# can-weichendecoder-magnet.net
KiCad netlist of a schematic drawn in EAGLE
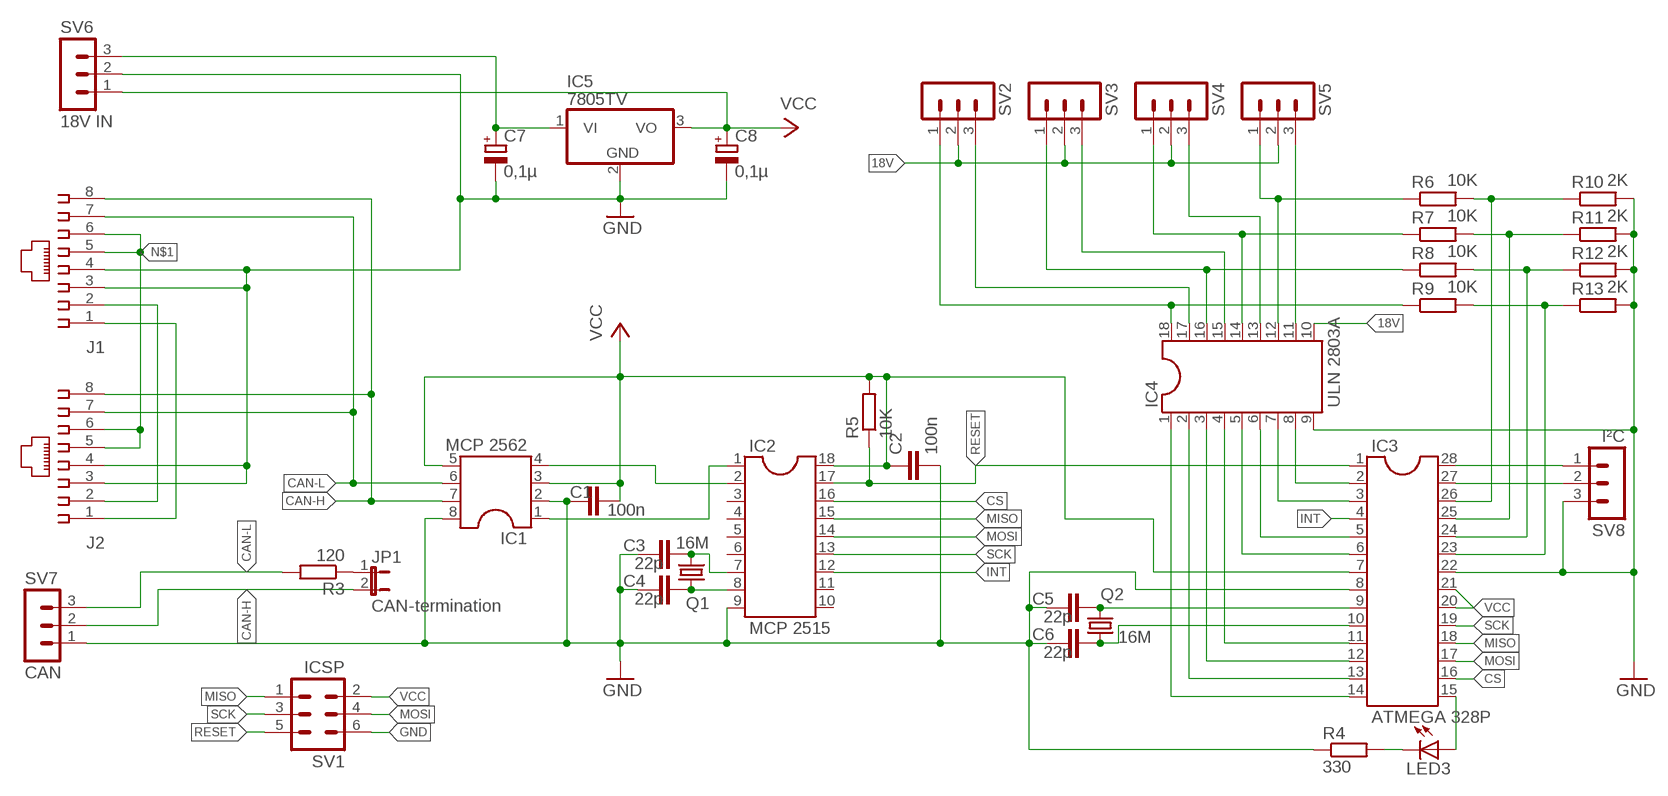
[diagram p0: schematic, sheet 1]

(export (version "E")
  (design (tool "Eeschema 10.0.6"))
  (components
    (comp (ref "C1")
      (value "100n")
      (footprint "eagle-import:C2.5-2")
      (libsource (lib "eagle-import") (part "C2.5/2"))
    )
    (comp (ref "C2")
      (value "100n")
      (footprint "eagle-import:C2.5-2")
      (libsource (lib "eagle-import") (part "C2.5/2"))
    )
    (comp (ref "C3")
      (value "22p")
      (footprint "eagle-import:C2.5-2")
      (libsource (lib "eagle-import") (part "C2.5/2"))
    )
    (comp (ref "C4")
      (value "22p")
      (footprint "eagle-import:C2.5-2")
      (libsource (lib "eagle-import") (part "C2.5/2"))
    )
    (comp (ref "C5")
      (value "22p")
      (footprint "eagle-import:C2.5-2")
      (libsource (lib "eagle-import") (part "C2.5/2"))
    )
    (comp (ref "C6")
      (value "22p")
      (footprint "eagle-import:C2.5-2")
      (libsource (lib "eagle-import") (part "C2.5/2"))
    )
    (comp (ref "C7")
      (value "0,1µ")
      (footprint "eagle-import:E2,5-6")
      (libsource (lib "eagle-import") (part "CPOL-EUE2.5-6"))
    )
    (comp (ref "C8")
      (value "0,1µ")
      (footprint "eagle-import:E2,5-6")
      (libsource (lib "eagle-import") (part "CPOL-EUE2.5-6"))
    )
    (comp (ref "IC1")
      (value "MCP 2562")
      (footprint "eagle-import:SOCKET-08")
      (libsource (lib "eagle-import") (part "DIL8S"))
    )
    (comp (ref "IC2")
      (value "MCP 2515")
      (footprint "eagle-import:SOCKET-18")
      (libsource (lib "eagle-import") (part "DIL18S"))
    )
    (comp (ref "IC3")
      (value "ATMEGA 328P")
      (footprint "eagle-import:DIL28-3")
      (libsource (lib "eagle-import") (part "DIL28-3"))
    )
    (comp (ref "IC4")
      (value "ULN 2803A")
      (footprint "eagle-import:SOCKET-18")
      (libsource (lib "eagle-import") (part "DIL18S"))
    )
    (comp (ref "IC5")
      (value "7805TV")
      (footprint "eagle-import:TO220V")
      (libsource (lib "eagle-import") (part "78TV05"))
    )
    (comp (ref "J1")
      (value "215877-7")
      (footprint "eagle-import:215877-7")
      (libsource (lib "eagle-import") (part "215877-7"))
    )
    (comp (ref "J2")
      (value "215877-7")
      (footprint "eagle-import:215877-7")
      (libsource (lib "eagle-import") (part "215877-7"))
    )
    (comp (ref "JP1")
      (value "CAN-termination")
      (footprint "eagle-import:JP1")
      (libsource (lib "eagle-import") (part "JP1E"))
    )
    (comp (ref "LED3")
      (value "LED5MM")
      (footprint "eagle-import:LED5MM")
      (libsource (lib "eagle-import") (part "LED5MM"))
    )
    (comp (ref "Q1")
      (value "16M")
      (footprint "eagle-import:HC49_S")
      (libsource (lib "eagle-import") (part "CRYSTALHC49S"))
    )
    (comp (ref "Q2")
      (value "16M")
      (footprint "eagle-import:HC49_S")
      (libsource (lib "eagle-import") (part "CRYSTALHC49S"))
    )
    (comp (ref "R3")
      (value "120")
      (footprint "eagle-import:0207_10")
      (libsource (lib "eagle-import") (part "R-EU_0207/10"))
    )
    (comp (ref "R4")
      (value "330")
      (footprint "eagle-import:0207_10")
      (libsource (lib "eagle-import") (part "R-EU_0207/10"))
    )
    (comp (ref "R5")
      (value "10K")
      (footprint "eagle-import:0207_10")
      (libsource (lib "eagle-import") (part "R-EU_0207/10"))
    )
    (comp (ref "R6")
      (value "10K")
      (footprint "eagle-import:0207_10")
      (libsource (lib "eagle-import") (part "R-EU_0207/10"))
    )
    (comp (ref "R7")
      (value "10K")
      (footprint "eagle-import:0207_10")
      (libsource (lib "eagle-import") (part "R-EU_0207/10"))
    )
    (comp (ref "R8")
      (value "10K")
      (footprint "eagle-import:0207_10")
      (libsource (lib "eagle-import") (part "R-EU_0207/10"))
    )
    (comp (ref "R9")
      (value "10K")
      (footprint "eagle-import:0207_10")
      (libsource (lib "eagle-import") (part "R-EU_0207/10"))
    )
    (comp (ref "R10")
      (value "2K")
      (footprint "eagle-import:0207_10")
      (libsource (lib "eagle-import") (part "R-EU_0207/10"))
    )
    (comp (ref "R11")
      (value "2K")
      (footprint "eagle-import:0207_10")
      (libsource (lib "eagle-import") (part "R-EU_0207/10"))
    )
    (comp (ref "R12")
      (value "2K")
      (footprint "eagle-import:0207_10")
      (libsource (lib "eagle-import") (part "R-EU_0207/10"))
    )
    (comp (ref "R13")
      (value "2K")
      (footprint "eagle-import:0207_10")
      (libsource (lib "eagle-import") (part "R-EU_0207/10"))
    )
    (comp (ref "SV1")
      (value "ICSP")
      (footprint "eagle-import:MA03-2")
      (libsource (lib "eagle-import") (part "MA03-2"))
    )
    (comp (ref "SV2")
      (value "MA03-1")
      (footprint "eagle-import:MA03-1")
      (libsource (lib "eagle-import") (part "MA03-1"))
    )
    (comp (ref "SV3")
      (value "MA03-1")
      (footprint "eagle-import:MA03-1")
      (libsource (lib "eagle-import") (part "MA03-1"))
    )
    (comp (ref "SV4")
      (value "MA03-1")
      (footprint "eagle-import:MA03-1")
      (libsource (lib "eagle-import") (part "MA03-1"))
    )
    (comp (ref "SV5")
      (value "MA03-1")
      (footprint "eagle-import:MA03-1")
      (libsource (lib "eagle-import") (part "MA03-1"))
    )
    (comp (ref "SV6")
      (value "18V IN")
      (footprint "eagle-import:MA03-1")
      (libsource (lib "eagle-import") (part "MA03-1"))
    )
    (comp (ref "SV7")
      (value "CAN")
      (footprint "eagle-import:MA03-1")
      (libsource (lib "eagle-import") (part "MA03-1"))
    )
    (comp (ref "SV8")
      (value "I²C")
      (footprint "eagle-import:MA03-1")
      (libsource (lib "eagle-import") (part "MA03-1"))
    )
  )
  (nets
    (net (code "1") (name "18V") (class "Default")
      (node (ref "C7") (pin "+") (pinfunction "+_+") (pintype "passive"))
      (node (ref "IC4") (pin "10") (pinfunction "10_10") (pintype "passive"))
      (node (ref "IC5") (pin "1") (pinfunction "VI_1") (pintype "input"))
      (node (ref "SV2") (pin "2") (pinfunction "2_2") (pintype "passive"))
      (node (ref "SV3") (pin "2") (pinfunction "2_2") (pintype "passive"))
      (node (ref "SV4") (pin "2") (pinfunction "2_2") (pintype "passive"))
      (node (ref "SV5") (pin "2") (pinfunction "2_2") (pintype "passive"))
      (node (ref "SV6") (pin "3") (pinfunction "3_3") (pintype "passive"))
    )
    (net (code "2") (name "CAN-H") (class "Default")
      (node (ref "IC1") (pin "7") (pinfunction "7_7") (pintype "passive"))
      (node (ref "J1") (pin "8") (pinfunction "8_8") (pintype "passive"))
      (node (ref "J2") (pin "8") (pinfunction "8_8") (pintype "passive"))
      (node (ref "JP1") (pin "2") (pinfunction "2_2") (pintype "passive"))
      (node (ref "SV7") (pin "2") (pinfunction "2_2") (pintype "passive"))
    )
    (net (code "3") (name "CAN-L") (class "Default")
      (node (ref "IC1") (pin "6") (pinfunction "6_6") (pintype "passive"))
      (node (ref "J1") (pin "7") (pinfunction "7_7") (pintype "passive"))
      (node (ref "J2") (pin "7") (pinfunction "7_7") (pintype "passive"))
      (node (ref "R3") (pin "2") (pinfunction "2_2") (pintype "passive"))
      (node (ref "SV7") (pin "3") (pinfunction "3_3") (pintype "passive"))
    )
    (net (code "4") (name "CS") (class "Default")
      (node (ref "IC2") (pin "16") (pinfunction "16_16") (pintype "passive"))
      (node (ref "IC3") (pin "16") (pinfunction "16_16") (pintype "passive"))
    )
    (net (code "5") (name "GND") (class "Default")
      (node (ref "C1") (pin "1") (pinfunction "1_1") (pintype "passive"))
      (node (ref "C2") (pin "2") (pinfunction "2_2") (pintype "passive"))
      (node (ref "C3") (pin "1") (pinfunction "1_1") (pintype "passive"))
      (node (ref "C4") (pin "1") (pinfunction "1_1") (pintype "passive"))
      (node (ref "C5") (pin "1") (pinfunction "1_1") (pintype "passive"))
      (node (ref "C6") (pin "1") (pinfunction "1_1") (pintype "passive"))
      (node (ref "C7") (pin "-") (pinfunction "-_-") (pintype "passive"))
      (node (ref "C8") (pin "-") (pinfunction "-_-") (pintype "passive"))
      (node (ref "IC1") (pin "2") (pinfunction "2_2") (pintype "passive"))
      (node (ref "IC1") (pin "8") (pinfunction "8_8") (pintype "passive"))
      (node (ref "IC2") (pin "9") (pinfunction "9_9") (pintype "passive"))
      (node (ref "IC3") (pin "22") (pinfunction "22_22") (pintype "passive"))
      (node (ref "IC3") (pin "8") (pinfunction "8_8") (pintype "passive"))
      (node (ref "IC4") (pin "9") (pinfunction "9_9") (pintype "passive"))
      (node (ref "IC5") (pin "2") (pinfunction "GND_2") (pintype "passive"))
      (node (ref "J1") (pin "3") (pinfunction "3_3") (pintype "passive"))
      (node (ref "J1") (pin "4") (pinfunction "4_4") (pintype "passive"))
      (node (ref "J2") (pin "3") (pinfunction "3_3") (pintype "passive"))
      (node (ref "J2") (pin "4") (pinfunction "4_4") (pintype "passive"))
      (node (ref "R10") (pin "2") (pinfunction "2_2") (pintype "passive"))
      (node (ref "R11") (pin "2") (pinfunction "2_2") (pintype "passive"))
      (node (ref "R12") (pin "2") (pinfunction "2_2") (pintype "passive"))
      (node (ref "R13") (pin "2") (pinfunction "2_2") (pintype "passive"))
      (node (ref "R4") (pin "1") (pinfunction "1_1") (pintype "passive"))
      (node (ref "SV1") (pin "6") (pinfunction "6_6") (pintype "passive"))
      (node (ref "SV6") (pin "2") (pinfunction "2_2") (pintype "passive"))
      (node (ref "SV7") (pin "1") (pinfunction "1_1") (pintype "passive"))
      (node (ref "SV8") (pin "3") (pinfunction "3_3") (pintype "passive"))
    )
    (net (code "6") (name "INT") (class "Default")
      (node (ref "IC2") (pin "12") (pinfunction "12_12") (pintype "passive"))
      (node (ref "IC3") (pin "4") (pinfunction "4_4") (pintype "passive"))
    )
    (net (code "7") (name "MISO") (class "Default")
      (node (ref "IC2") (pin "15") (pinfunction "15_15") (pintype "passive"))
      (node (ref "IC3") (pin "18") (pinfunction "18_18") (pintype "passive"))
      (node (ref "SV1") (pin "1") (pinfunction "1_1") (pintype "passive"))
    )
    (net (code "8") (name "MOSI") (class "Default")
      (node (ref "IC2") (pin "14") (pinfunction "14_14") (pintype "passive"))
      (node (ref "IC3") (pin "17") (pinfunction "17_17") (pintype "passive"))
      (node (ref "SV1") (pin "4") (pinfunction "4_4") (pintype "passive"))
    )
    (net (code "9") (name "N$1") (class "Default")
      (node (ref "J1") (pin "5") (pinfunction "5_5") (pintype "passive"))
      (node (ref "J1") (pin "6") (pinfunction "6_6") (pintype "passive"))
      (node (ref "J2") (pin "5") (pinfunction "5_5") (pintype "passive"))
      (node (ref "J2") (pin "6") (pinfunction "6_6") (pintype "passive"))
    )
    (net (code "10") (name "Net-(C3-Pad2)") (class "Default")
      (node (ref "C3") (pin "2") (pinfunction "2_2") (pintype "passive"))
      (node (ref "IC2") (pin "7") (pinfunction "7_7") (pintype "passive"))
      (node (ref "Q1") (pin "2") (pinfunction "2_2") (pintype "passive"))
    )
    (net (code "11") (name "Net-(C4-Pad2)") (class "Default")
      (node (ref "C4") (pin "2") (pinfunction "2_2") (pintype "passive"))
      (node (ref "IC2") (pin "8") (pinfunction "8_8") (pintype "passive"))
      (node (ref "Q1") (pin "1") (pinfunction "1_1") (pintype "passive"))
    )
    (net (code "12") (name "Net-(C5-Pad2)") (class "Default")
      (node (ref "C5") (pin "2") (pinfunction "2_2") (pintype "passive"))
      (node (ref "IC3") (pin "9") (pinfunction "9_9") (pintype "passive"))
      (node (ref "Q2") (pin "2") (pinfunction "2_2") (pintype "passive"))
    )
    (net (code "13") (name "Net-(C6-Pad2)") (class "Default")
      (node (ref "C6") (pin "2") (pinfunction "2_2") (pintype "passive"))
      (node (ref "IC3") (pin "10") (pinfunction "10_10") (pintype "passive"))
      (node (ref "Q2") (pin "1") (pinfunction "1_1") (pintype "passive"))
    )
    (net (code "14") (name "Net-(IC1-Pad1)") (class "Default")
      (node (ref "IC1") (pin "1") (pinfunction "1_1") (pintype "passive"))
      (node (ref "IC2") (pin "1") (pinfunction "1_1") (pintype "passive"))
    )
    (net (code "15") (name "Net-(IC1-Pad4)") (class "Default")
      (node (ref "IC1") (pin "4") (pinfunction "4_4") (pintype "passive"))
      (node (ref "IC2") (pin "2") (pinfunction "2_2") (pintype "passive"))
    )
    (net (code "16") (name "Net-(IC3-Pad2)") (class "Default")
      (node (ref "IC3") (pin "2") (pinfunction "2_2") (pintype "passive"))
      (node (ref "IC4") (pin "8") (pinfunction "8_8") (pintype "passive"))
    )
    (net (code "17") (name "Net-(IC3-Pad3)") (class "Default")
      (node (ref "IC3") (pin "3") (pinfunction "3_3") (pintype "passive"))
      (node (ref "IC4") (pin "7") (pinfunction "7_7") (pintype "passive"))
    )
    (net (code "18") (name "Net-(IC3-Pad5)") (class "Default")
      (node (ref "IC3") (pin "5") (pinfunction "5_5") (pintype "passive"))
      (node (ref "IC4") (pin "6") (pinfunction "6_6") (pintype "passive"))
    )
    (net (code "19") (name "Net-(IC3-Pad6)") (class "Default")
      (node (ref "IC3") (pin "6") (pinfunction "6_6") (pintype "passive"))
      (node (ref "IC4") (pin "5") (pinfunction "5_5") (pintype "passive"))
    )
    (net (code "20") (name "Net-(IC3-Pad11)") (class "Default")
      (node (ref "IC3") (pin "11") (pinfunction "11_11") (pintype "passive"))
      (node (ref "IC4") (pin "4") (pinfunction "4_4") (pintype "passive"))
    )
    (net (code "21") (name "Net-(IC3-Pad12)") (class "Default")
      (node (ref "IC3") (pin "12") (pinfunction "12_12") (pintype "passive"))
      (node (ref "IC4") (pin "3") (pinfunction "3_3") (pintype "passive"))
    )
    (net (code "22") (name "Net-(IC3-Pad13)") (class "Default")
      (node (ref "IC3") (pin "13") (pinfunction "13_13") (pintype "passive"))
      (node (ref "IC4") (pin "2") (pinfunction "2_2") (pintype "passive"))
    )
    (net (code "23") (name "Net-(IC3-Pad14)") (class "Default")
      (node (ref "IC3") (pin "14") (pinfunction "14_14") (pintype "passive"))
      (node (ref "IC4") (pin "1") (pinfunction "1_1") (pintype "passive"))
    )
    (net (code "24") (name "Net-(IC3-Pad15)") (class "Default")
      (node (ref "IC3") (pin "15") (pinfunction "15_15") (pintype "passive"))
      (node (ref "LED3") (pin "A") (pinfunction "A_A") (pintype "passive"))
    )
    (net (code "25") (name "Net-(IC3-Pad23)") (class "Default")
      (node (ref "IC3") (pin "23") (pinfunction "23_23") (pintype "passive"))
      (node (ref "R13") (pin "1") (pinfunction "1_1") (pintype "passive"))
      (node (ref "R9") (pin "2") (pinfunction "2_2") (pintype "passive"))
    )
    (net (code "26") (name "Net-(IC3-Pad24)") (class "Default")
      (node (ref "IC3") (pin "24") (pinfunction "24_24") (pintype "passive"))
      (node (ref "R12") (pin "1") (pinfunction "1_1") (pintype "passive"))
      (node (ref "R8") (pin "2") (pinfunction "2_2") (pintype "passive"))
    )
    (net (code "27") (name "Net-(IC3-Pad25)") (class "Default")
      (node (ref "IC3") (pin "25") (pinfunction "25_25") (pintype "passive"))
      (node (ref "R11") (pin "1") (pinfunction "1_1") (pintype "passive"))
      (node (ref "R7") (pin "2") (pinfunction "2_2") (pintype "passive"))
    )
    (net (code "28") (name "Net-(IC3-Pad26)") (class "Default")
      (node (ref "IC3") (pin "26") (pinfunction "26_26") (pintype "passive"))
      (node (ref "R10") (pin "1") (pinfunction "1_1") (pintype "passive"))
      (node (ref "R6") (pin "2") (pinfunction "2_2") (pintype "passive"))
    )
    (net (code "29") (name "Net-(IC3-Pad27)") (class "Default")
      (node (ref "IC3") (pin "27") (pinfunction "27_27") (pintype "passive"))
      (node (ref "SV8") (pin "2") (pinfunction "2_2") (pintype "passive"))
    )
    (net (code "30") (name "Net-(IC3-Pad28)") (class "Default")
      (node (ref "IC3") (pin "28") (pinfunction "28_28") (pintype "passive"))
      (node (ref "SV8") (pin "1") (pinfunction "1_1") (pintype "passive"))
    )
    (net (code "31") (name "Net-(IC4-Pad11)") (class "Default")
      (node (ref "IC4") (pin "11") (pinfunction "11_11") (pintype "passive"))
      (node (ref "SV5") (pin "3") (pinfunction "3_3") (pintype "passive"))
    )
    (net (code "32") (name "Net-(IC4-Pad12)") (class "Default")
      (node (ref "IC4") (pin "12") (pinfunction "12_12") (pintype "passive"))
      (node (ref "R6") (pin "1") (pinfunction "1_1") (pintype "passive"))
      (node (ref "SV5") (pin "1") (pinfunction "1_1") (pintype "passive"))
    )
    (net (code "33") (name "Net-(IC4-Pad13)") (class "Default")
      (node (ref "IC4") (pin "13") (pinfunction "13_13") (pintype "passive"))
      (node (ref "SV4") (pin "3") (pinfunction "3_3") (pintype "passive"))
    )
    (net (code "34") (name "Net-(IC4-Pad14)") (class "Default")
      (node (ref "IC4") (pin "14") (pinfunction "14_14") (pintype "passive"))
      (node (ref "R7") (pin "1") (pinfunction "1_1") (pintype "passive"))
      (node (ref "SV4") (pin "1") (pinfunction "1_1") (pintype "passive"))
    )
    (net (code "35") (name "Net-(IC4-Pad15)") (class "Default")
      (node (ref "IC4") (pin "15") (pinfunction "15_15") (pintype "passive"))
      (node (ref "SV3") (pin "3") (pinfunction "3_3") (pintype "passive"))
    )
    (net (code "36") (name "Net-(IC4-Pad16)") (class "Default")
      (node (ref "IC4") (pin "16") (pinfunction "16_16") (pintype "passive"))
      (node (ref "R8") (pin "1") (pinfunction "1_1") (pintype "passive"))
      (node (ref "SV3") (pin "1") (pinfunction "1_1") (pintype "passive"))
    )
    (net (code "37") (name "Net-(IC4-Pad17)") (class "Default")
      (node (ref "IC4") (pin "17") (pinfunction "17_17") (pintype "passive"))
      (node (ref "SV2") (pin "3") (pinfunction "3_3") (pintype "passive"))
    )
    (net (code "38") (name "Net-(IC4-Pad18)") (class "Default")
      (node (ref "IC4") (pin "18") (pinfunction "18_18") (pintype "passive"))
      (node (ref "R9") (pin "1") (pinfunction "1_1") (pintype "passive"))
      (node (ref "SV2") (pin "1") (pinfunction "1_1") (pintype "passive"))
    )
    (net (code "39") (name "Net-(J1-Pad1)") (class "Default")
      (node (ref "J1") (pin "1") (pinfunction "1_1") (pintype "passive"))
      (node (ref "J2") (pin "1") (pinfunction "1_1") (pintype "passive"))
    )
    (net (code "40") (name "Net-(J1-Pad2)") (class "Default")
      (node (ref "J1") (pin "2") (pinfunction "2_2") (pintype "passive"))
      (node (ref "J2") (pin "2") (pinfunction "2_2") (pintype "passive"))
    )
    (net (code "41") (name "Net-(JP1-Pad1)") (class "Default")
      (node (ref "JP1") (pin "1") (pinfunction "1_1") (pintype "passive"))
      (node (ref "R3") (pin "1") (pinfunction "1_1") (pintype "passive"))
    )
    (net (code "42") (name "Net-(LED3-C)") (class "Default")
      (node (ref "LED3") (pin "K") (pinfunction "C_K") (pintype "passive"))
      (node (ref "R4") (pin "2") (pinfunction "2_2") (pintype "passive"))
    )
    (net (code "43") (name "RESET") (class "Default")
      (node (ref "IC2") (pin "17") (pinfunction "17_17") (pintype "passive"))
      (node (ref "IC3") (pin "1") (pinfunction "1_1") (pintype "passive"))
      (node (ref "R5") (pin "1") (pinfunction "1_1") (pintype "passive"))
      (node (ref "SV1") (pin "5") (pinfunction "5_5") (pintype "passive"))
    )
    (net (code "44") (name "SCK") (class "Default")
      (node (ref "IC2") (pin "13") (pinfunction "13_13") (pintype "passive"))
      (node (ref "IC3") (pin "19") (pinfunction "19_19") (pintype "passive"))
      (node (ref "SV1") (pin "3") (pinfunction "3_3") (pintype "passive"))
    )
    (net (code "45") (name "VCC") (class "Default")
      (node (ref "C1") (pin "2") (pinfunction "2_2") (pintype "passive"))
      (node (ref "C2") (pin "1") (pinfunction "1_1") (pintype "passive"))
      (node (ref "C8") (pin "+") (pinfunction "+_+") (pintype "passive"))
      (node (ref "IC1") (pin "3") (pinfunction "3_3") (pintype "passive"))
      (node (ref "IC1") (pin "5") (pinfunction "5_5") (pintype "passive"))
      (node (ref "IC2") (pin "18") (pinfunction "18_18") (pintype "passive"))
      (node (ref "IC3") (pin "20") (pinfunction "20_20") (pintype "passive"))
      (node (ref "IC3") (pin "21") (pinfunction "21_21") (pintype "passive"))
      (node (ref "IC3") (pin "7") (pinfunction "7_7") (pintype "passive"))
      (node (ref "IC5") (pin "3") (pinfunction "VO_3") (pintype "passive"))
      (node (ref "R5") (pin "2") (pinfunction "2_2") (pintype "passive"))
      (node (ref "SV1") (pin "2") (pinfunction "2_2") (pintype "passive"))
      (node (ref "SV6") (pin "1") (pinfunction "1_1") (pintype "passive"))
    )
    (net (code "46") (name "unconnected-(IC2-Pad3)") (class "Default")
      (node (ref "IC2") (pin "3") (pinfunction "3_3") (pintype "passive"))
    )
    (net (code "47") (name "unconnected-(IC2-Pad4)") (class "Default")
      (node (ref "IC2") (pin "4") (pinfunction "4_4") (pintype "passive"))
    )
    (net (code "48") (name "unconnected-(IC2-Pad5)") (class "Default")
      (node (ref "IC2") (pin "5") (pinfunction "5_5") (pintype "passive"))
    )
    (net (code "49") (name "unconnected-(IC2-Pad6)") (class "Default")
      (node (ref "IC2") (pin "6") (pinfunction "6_6") (pintype "passive"))
    )
    (net (code "50") (name "unconnected-(IC2-Pad10)") (class "Default")
      (node (ref "IC2") (pin "10") (pinfunction "10_10") (pintype "passive"))
    )
    (net (code "51") (name "unconnected-(IC2-Pad11)") (class "Default")
      (node (ref "IC2") (pin "11") (pinfunction "11_11") (pintype "passive"))
    )
  )
)
